# Power.net
KiCad netlist of a schematic drawn in Altium Designer
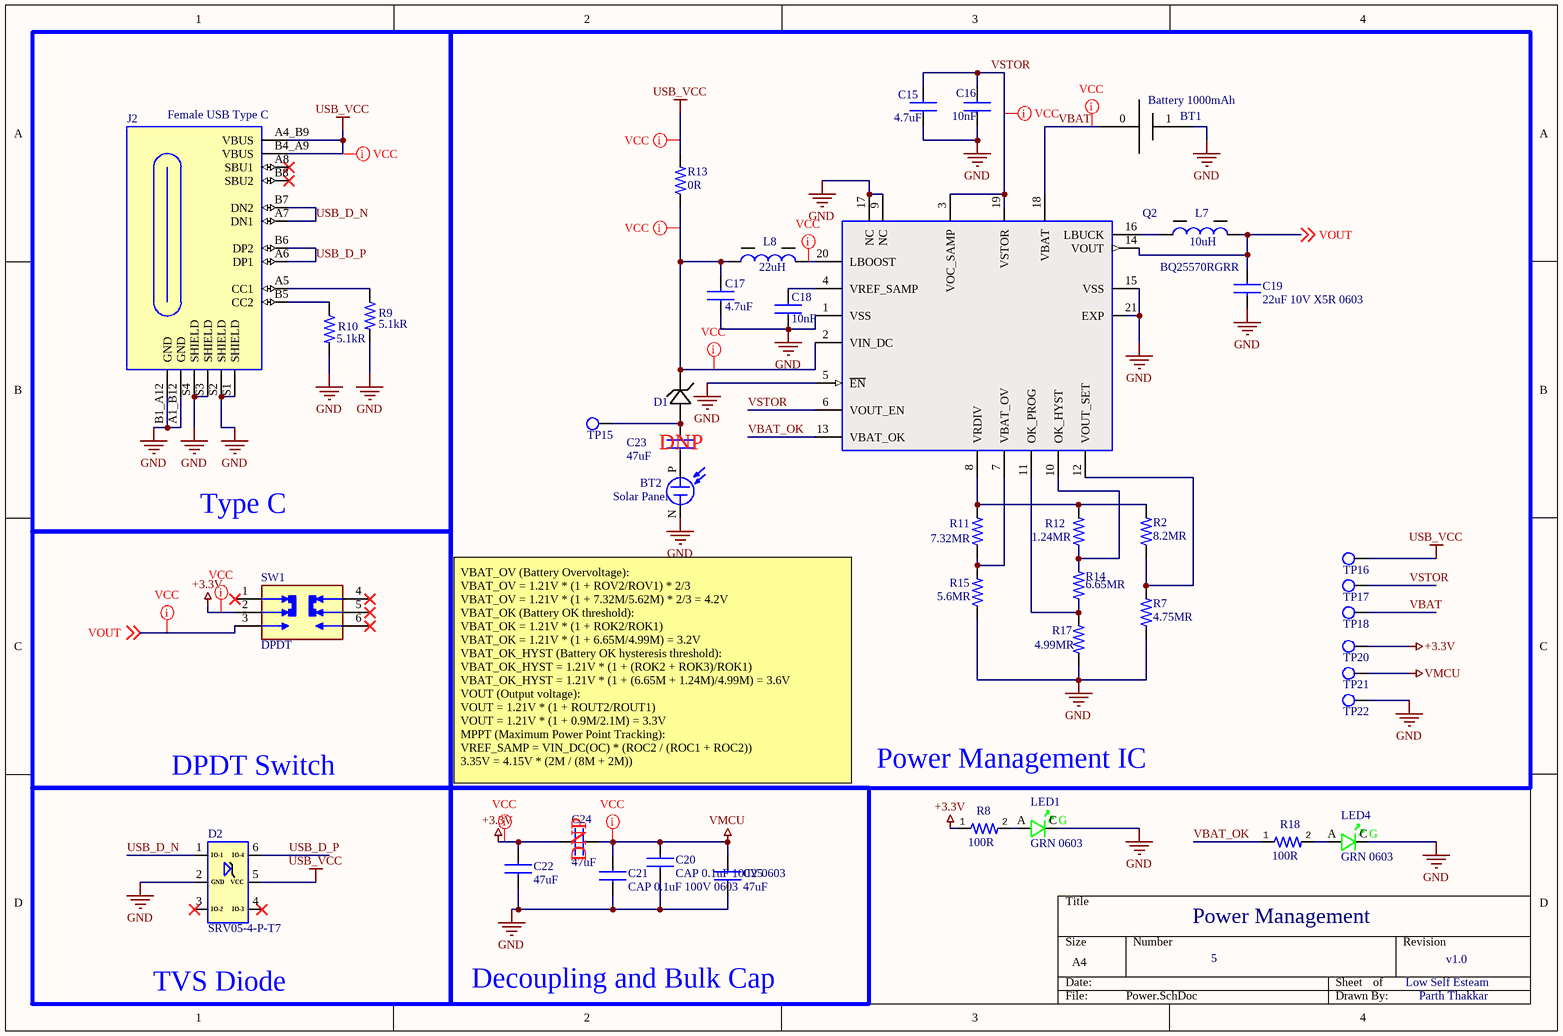
[diagram p0: Power.SchDoc]

(export (version "E")
  (design (tool "Eeschema 10.0.6"))
  (components
    (comp (ref "BT1")
      (value "Battery 1000mAh")
      (footprint "Battery")
      (description "Batt Lith-ion 3.7V 1.05AH 404852")
      (fields
        (field (name "MANUFACTURER") "GlobTek")
        (field (name "MANUFACTURER PART NUMBER") "BL1200P4054481S1PCAC")
      )
      (libsource (lib "Keyboard_parts") (part "Battery 1000mAh"))
    )
    (comp (ref "BT2")
      (value "Solar Panel")
      (footprint "Solar panel")
      (description "Monocryst Solar Cell 184MW 4.15V")
      (fields (field (name "MANUFACTURER") "ANYSOLAR") (field (name "MANUFACTURER PART NUMBER") "SM141K06L"))
      (libsource (lib "Keyboard_parts") (part "Solar Panel"))
    )
    (comp (ref "C15")
      (value "4.7uF")
      (footprint "Capacitor 0603")
      (fields
        (field (name "MANUFACTURER") "Murata")
        (field (name "MANUFACTURER PART NUMBER") "GRT188R61E475KE13D")
        (field (name "Comment") "CAP 4.7uF 25V 0603")
      )
      (libsource (lib "Keyboard_parts") (part "CAP 4.7uF 25V 0603"))
    )
    (comp (ref "C16")
      (value "10nF")
      (footprint "Capacitor 0603")
      (fields
        (field (name "MANUFACTURER") "Murata")
        (field (name "MANUFACTURER PART NUMBER") "GCM188R72A103KA37D")
        (field (name "Comment") "CAP 10nF 100V 0603")
      )
      (libsource (lib "Keyboard_parts") (part "CAP 10nF 100V 0603"))
    )
    (comp (ref "C17")
      (value "4.7uF")
      (footprint "Capacitor 0603")
      (fields
        (field (name "MANUFACTURER") "Murata")
        (field (name "MANUFACTURER PART NUMBER") "GRT188R61E475KE13D")
        (field (name "Comment") "CAP 4.7uF 25V 0603")
      )
      (libsource (lib "Keyboard_parts") (part "CAP 4.7uF 25V 0603"))
    )
    (comp (ref "C18")
      (value "10nF")
      (footprint "Capacitor 0603")
      (fields
        (field (name "MANUFACTURER") "Murata")
        (field (name "MANUFACTURER PART NUMBER") "GCM188R72A103KA37D")
        (field (name "Comment") "CAP 10nF 100V 0603")
      )
      (libsource (lib "Keyboard_parts") (part "CAP 10nF 100V 0603"))
    )
    (comp (ref "C19")
      (value "22uF 10V X5R 0603")
      (footprint "Capacitor 0603")
      (fields
        (field (name "MANUFACTURER") "Murata")
        (field (name "MANUFACTURER PART NUMBER") "GRM188R61A226ME15D")
        (field (name "TOLERANCE") "20 %")
      )
      (libsource (lib "Keyboard_parts") (part "CAP 22uF 6.3V 0603"))
    )
    (comp (ref "C20")
      (value "CAP 0.1uF 100V 0603")
      (footprint "Capacitor 0603")
      (fields
        (field (name "MANUFACTURER") "Murata")
        (field (name "MANUFACTURER PART NUMBER") "GCM188R72A103KA37D")
      )
      (libsource (lib "Keyboard_parts") (part "CAP 0.1uF 100V 0603"))
    )
    (comp (ref "C21")
      (value "CAP 0.1uF 100V 0603")
      (footprint "Capacitor 0603")
      (fields
        (field (name "MANUFACTURER") "Murata")
        (field (name "MANUFACTURER PART NUMBER") "GCM188R72A103KA37D")
      )
      (libsource (lib "Keyboard_parts") (part "CAP 0.1uF 100V 0603"))
    )
    (comp (ref "C22")
      (value "47uF")
      (footprint "Capacitor 0805")
      (description "Multilayer Ceramic Capacitors MLCC - SMD/SMT 0805 47uF 10volts *Derate Voltage/Temp")
      (fields
        (field (name "MANUFACTURER") "Murata")
        (field (name "MANUFACTURER PART NUMBER") "GRM21BR61A476ME15K")
      )
      (libsource (lib "Keyboard_parts") (part "CAP 47uF 10V 0805"))
    )
    (comp (ref "C23")
      (value "47uF")
      (footprint "CAPACITOR 0805")
      (description "Multilayer Ceramic Capacitors MLCC - SMD/SMT 0805 47uF 10volts *Derate Voltage/Temp")
      (fields
        (field (name "MANUFACTURER") "Murata")
        (field (name "MANUFACTURER PART NUMBER") "GRM21BR61A476ME15K")
      )
      (libsource (lib "InsaneIntegratedLib") (part "CAP 47uF 10V 0805"))
    )
    (comp (ref "C24")
      (value "47uF")
      (footprint "CAPACITOR 0805")
      (description "Multilayer Ceramic Capacitors MLCC - SMD/SMT 0805 47uF 10volts *Derate Voltage/Temp")
      (fields
        (field (name "MANUFACTURER") "Murata")
        (field (name "MANUFACTURER PART NUMBER") "GRM21BR61A476ME15K")
      )
      (libsource (lib "InsaneIntegratedLib") (part "CAP 47uF 10V 0805"))
    )
    (comp (ref "C25")
      (value "47uF")
      (footprint "Capacitor 0805")
      (description "Multilayer Ceramic Capacitors MLCC - SMD/SMT 0805 47uF 10volts *Derate Voltage/Temp")
      (fields
        (field (name "MANUFACTURER") "Murata")
        (field (name "MANUFACTURER PART NUMBER") "GRM21BR61A476ME15K")
      )
      (libsource (lib "Keyboard_parts") (part "CAP 47uF 10V 0805"))
    )
    (comp (ref "D1")
      (value "Diode Schottky")
      (footprint "Diode Schottky")
      (description "Rectifier Diode, Schottky, 1 Phase, 1 Element, 1A, 15V V(RRM), Silicon, DO-214BA")
      (fields
        (field (name "MANUFACTURER") "Microchip")
        (field (name "MANUFACTURER PART NUMBER") "LSM115JE3/TR13")
      )
      (libsource (lib "InsaneIntegratedLib") (part "Diode Schottky"))
    )
    (comp (ref "D2")
      (value "SRV05-4-P-T7")
      (footprint "TVS")
      (description "Trans Voltage Suppressor Diode, 300W, 5V V(RWM), Unidirectional, 1 Element, Silicon")
      (fields (field (name "LCSC PART#") "C85364") (field (name "MANUFACTURER") "Semtech"))
      (libsource (lib "Keyboard_parts") (part "D_TVS_Diode"))
    )
    (comp (ref "J2")
      (value "Female USB Type C")
      (footprint "Type C")
      (fields (field (name "MANUFACTURER PART NUMBER") "USB4125-GF-A_REVA2"))
      (libsource (lib "Keyboard_parts") (part "USB-C Power Connector"))
    )
    (comp (ref "L7")
      (value "IND 10uH 1111")
      (footprint "IND 10uH (1x3.2)")
      (description "General Purpose Inductor, 10uH, 30%, 1 Element, Ferrite-Core, SMD, 1111")
      (fields
        (field (name "MANUFACTURER") "Wurth Electronics")
        (field (name "MANUFACTURER PART NUMBER") "744029100")
        (field (name "INDUCTANCE-NOM (L)") "10uH")
      )
      (libsource (lib "Keyboard_parts") (part "IND 10uH 1111"))
    )
    (comp (ref "L8")
      (value "IND 22uH 1515")
      (footprint "IND 22uH (1.6x4.3)")
      (description "General Purpose Inductor, 22uH, 30%, 1 Element, Ferrite-Core, SMD, 1515")
      (fields
        (field (name "MANUFACTURER") "Wurth Electronics")
        (field (name "MANUFACTURER PART NUMBER") "744031220")
        (field (name "INDUCTANCE-NOM (L)") "22uH")
      )
      (libsource (lib "Keyboard_parts") (part "IND 22uH 1515"))
    )
    (comp (ref "LED1")
      (value "GRN 0603")
      (footprint "LED 0603")
      (description "LED, 0603, GREEN, 430MCD, 520NM")
      (fields
        (field (name "MANUFACTURER") "Wurth Electronics")
        (field (name "MANUFACTURER PART NUMBER") "150060GS75000")
      )
      (libsource (lib "InsaneIntegratedLib") (part "LED Green 0603"))
    )
    (comp (ref "LED4")
      (value "GRN 0603")
      (footprint "LED 0603")
      (description "LED, 0603, GREEN, 430MCD, 520NM")
      (fields
        (field (name "MANUFACTURER") "Wurth Electronics")
        (field (name "MANUFACTURER PART NUMBER") "150060GS75000")
      )
      (libsource (lib "InsaneIntegratedLib") (part "LED Green 0603"))
    )
    (comp (ref "Q2")
      (value "BQ25570RGRR")
      (footprint "BQ25570RGRR")
      (description "Power Supply Support Circuit, Adjustable, 1 Channel, PQCC20")
      (fields (field (name "MANUFACTURER") "Texas Instruments"))
      (libsource (lib "Keyboard_parts") (part "BQ25570RGRR"))
    )
    (comp (ref "R2")
      (value "8.2MR")
      (footprint "Resistor 0603")
      (fields
        (field (name "MANUFACTURER") "Yageo")
        (field (name "MANUFACTURER PART NUMBER") "RC0603JR-078M2L")
        (field (name "TOLERANCE") "5%")
      )
      (libsource (lib "InsaneIntegratedLib") (part "RES 8.2M 0603"))
    )
    (comp (ref "R7")
      (value "4.75MR")
      (footprint "Resistor 0603")
      (fields
        (field (name "MANUFACTURER") "Yageo")
        (field (name "MANUFACTURER PART NUMBER") "RC0603FR-074M75L")
        (field (name "TOLERANCE") "1%")
      )
      (libsource (lib "InsaneIntegratedLib") (part "RES 4.75M 0603"))
    )
    (comp (ref "R8")
      (value "100R")
      (footprint "Resistor 0603")
      (fields
        (field (name "MANUFACTURER") "Yageo")
        (field (name "MANUFACTURER PART NUMBER") "RC0603FR-07100RL")
        (field (name "TOLERANCE") "1%")
      )
      (libsource (lib "InsaneIntegratedLib") (part "RES 100R 0603"))
    )
    (comp (ref "R9")
      (value "5.1kR")
      (footprint "Resistor 0603")
      (fields
        (field (name "MANUFACTURER") "Yageo")
        (field (name "MANUFACTURER PART NUMBER") "RC0603FR-075K1L")
        (field (name "TOLERANCE") "1%")
      )
      (libsource (lib "Keyboard_parts") (part "RES 5.1K 0603"))
    )
    (comp (ref "R10")
      (value "5.1kR")
      (footprint "Resistor 0603")
      (fields
        (field (name "MANUFACTURER") "Yageo")
        (field (name "MANUFACTURER PART NUMBER") "RC0603FR-075K1L")
        (field (name "TOLERANCE") "1%")
      )
      (libsource (lib "Keyboard_parts") (part "RES 5.1K 0603"))
    )
    (comp (ref "R11")
      (value "7.32MR")
      (footprint "Resistor 0603")
      (fields
        (field (name "MANUFACTURER") "Yageo")
        (field (name "MANUFACTURER PART NUMBER") "RC0402FR-077M32L")
        (field (name "TOLERANCE") "1%")
      )
      (libsource (lib "Keyboard_parts") (part "RES 7.32M 0603"))
    )
    (comp (ref "R12")
      (value "1.24MR")
      (footprint "Resistor 0603")
      (fields
        (field (name "MANUFACTURER") "Yageo")
        (field (name "MANUFACTURER PART NUMBER") "RC0603FR-071M24L")
        (field (name "TOLERANCE") "1%")
      )
      (libsource (lib "Keyboard_parts") (part "RES 1.24M 0603"))
    )
    (comp (ref "R13")
      (value "0R")
      (footprint "Resistor 0402")
      (description "Metal Glaze/thick Film, 0.0625W, 0ohm, Surface Mount, 0402")
      (fields
        (field (name "MANUFACTURER") "Yageo")
        (field (name "MANUFACTURER PART NUMBER") "RC0402JR-070RL")
      )
      (libsource (lib "Keyboard_parts") (part "RES 0R 0402"))
    )
    (comp (ref "R14")
      (value "6.65MR")
      (footprint "Resistor 0603")
      (fields
        (field (name "MANUFACTURER") "Vishay")
        (field (name "MANUFACTURER PART NUMBER") "CRCW06036M65FKEA")
        (field (name "TOLERANCE") "1%")
      )
      (libsource (lib "Keyboard_parts") (part "RES 6.65M 0603"))
    )
    (comp (ref "R15")
      (value "5.6MR")
      (footprint "Resistor 0603")
      (fields
        (field (name "MANUFACTURER") "Yageo")
        (field (name "MANUFACTURER PART NUMBER") "RC0603JR-075M6L")
        (field (name "TOLERANCE") "5%")
      )
      (libsource (lib "Keyboard_parts") (part "RES 5.62M 0603"))
    )
    (comp (ref "R17")
      (value "4.99MR")
      (footprint "Resistor 0603")
      (fields
        (field (name "MANUFACTURER") "Yageo")
        (field (name "MANUFACTURER PART NUMBER") "RC0603FR-074M99L")
        (field (name "TOLERANCE") "1%")
      )
      (libsource (lib "Keyboard_parts") (part "RES 4.99M 0603"))
    )
    (comp (ref "R18")
      (value "100R")
      (footprint "Resistor 0603")
      (fields
        (field (name "MANUFACTURER") "Yageo")
        (field (name "MANUFACTURER PART NUMBER") "RC0603FR-07100RL")
        (field (name "TOLERANCE") "1%")
      )
      (libsource (lib "InsaneIntegratedLib") (part "RES 100R 0603"))
    )
    (comp (ref "SW1")
      (value "DPDT")
      (footprint "DPDT")
      (description "Slide Switch, DPDT, Latched, Solder Terminal, Through Hole-right Angle")
      (fields (field (name "MANUFACTURER") "E-Switch") (field (name "MANUFACTURER PART NUMBER") "EG2208"))
      (libsource (lib "Keyboard_parts") (part "DPDT"))
    )
    (comp (ref "TP15")
      (value "Test Point")
      (footprint "Test point")
      (description "Test points")
      (libsource (lib "Keyboard_parts") (part "Test Point"))
    )
    (comp (ref "TP16")
      (value "Test point")
      (footprint "Test Point")
      (libsource (lib "Keyboard_parts") (part "Test point"))
    )
    (comp (ref "TP17")
      (value "Test point")
      (footprint "Test Point")
      (libsource (lib "Keyboard_parts") (part "Test point"))
    )
    (comp (ref "TP18")
      (value "Test point")
      (footprint "Test Point")
      (libsource (lib "Keyboard_parts") (part "Test point"))
    )
    (comp (ref "TP20")
      (value "Test point")
      (footprint "Test Point")
      (libsource (lib "Keyboard_parts") (part "Test point"))
    )
    (comp (ref "TP21")
      (value "Test point")
      (footprint "Test Point")
      (libsource (lib "Keyboard_parts") (part "Test point"))
    )
    (comp (ref "TP22")
      (value "Test point")
      (footprint "Test Point")
      (libsource (lib "Keyboard_parts") (part "Test point"))
    )
  )
  (nets
    (net (code "1") (name "+3.3V") (class "Default")
      (node (ref "C22") (pin "1") (pinfunction "1_1") (pintype "passive"))
      (node (ref "C24") (pin "1") (pinfunction "1_1") (pintype "passive"))
      (node (ref "R8") (pin "1") (pinfunction "1_1") (pintype "passive"))
      (node (ref "SW1") (pin "2") (pinfunction "2_2") (pintype "passive"))
      (node (ref "TP20") (pin "1") (pinfunction "1_1") (pintype "passive"))
    )
    (net (code "2") (name "/USB_D_N") (class "Default")
      (node (ref "D2") (pin "1") (pinfunction "IO-1_1") (pintype "passive"))
      (node (ref "J2") (pin "A7") (pinfunction "DN1_A7") (pintype "bidirectional"))
      (node (ref "J2") (pin "B7") (pinfunction "DN2_B7") (pintype "bidirectional"))
    )
    (net (code "3") (name "/USB_D_P") (class "Default")
      (node (ref "D2") (pin "6") (pinfunction "IO-4_6") (pintype "passive"))
      (node (ref "J2") (pin "A6") (pinfunction "DP1_A6") (pintype "bidirectional"))
      (node (ref "J2") (pin "B6") (pinfunction "DP2_B6") (pintype "bidirectional"))
    )
    (net (code "4") (name "/VBAT") (class "Default")
      (node (ref "BT1") (pin "0") (pinfunction "VCC_0") (pintype "passive"))
      (node (ref "Q2") (pin "18") (pinfunction "VBAT_18") (pintype "power_in"))
      (node (ref "TP18") (pin "1") (pinfunction "1_1") (pintype "passive"))
    )
    (net (code "5") (name "/VBAT_OK") (class "Default")
      (node (ref "Q2") (pin "13") (pinfunction "VBAT_OK_13") (pintype "passive"))
      (node (ref "R18") (pin "1") (pinfunction "1_1") (pintype "passive"))
    )
    (net (code "6") (name "/VSTOR") (class "Default")
      (node (ref "C15") (pin "1") (pinfunction "1_1") (pintype "passive"))
      (node (ref "C16") (pin "1") (pinfunction "1_1") (pintype "passive"))
      (node (ref "Q2") (pin "19") (pinfunction "VSTOR_19") (pintype "passive"))
      (node (ref "Q2") (pin "3") (pinfunction "VOC_SAMP_3") (pintype "passive"))
      (node (ref "Q2") (pin "6") (pinfunction "VOUT_EN_6") (pintype "passive"))
      (node (ref "TP17") (pin "1") (pinfunction "1_1") (pintype "passive"))
    )
    (net (code "7") (name "GND") (class "Default")
      (node (ref "BT1") (pin "1") (pinfunction "GND_1") (pintype "passive"))
      (node (ref "BT2") (pin "N") (pinfunction "N_N") (pintype "passive"))
      (node (ref "C15") (pin "2") (pinfunction "2_2") (pintype "passive"))
      (node (ref "C16") (pin "2") (pinfunction "2_2") (pintype "passive"))
      (node (ref "C17") (pin "2") (pinfunction "2_2") (pintype "passive"))
      (node (ref "C18") (pin "1") (pinfunction "1_1") (pintype "passive"))
      (node (ref "C19") (pin "2") (pinfunction "2_2") (pintype "passive"))
      (node (ref "C20") (pin "2") (pinfunction "2_2") (pintype "passive"))
      (node (ref "C21") (pin "2") (pinfunction "2_2") (pintype "passive"))
      (node (ref "C22") (pin "2") (pinfunction "2_2") (pintype "passive"))
      (node (ref "C25") (pin "2") (pinfunction "2_2") (pintype "passive"))
      (node (ref "D2") (pin "2") (pinfunction "GND_2") (pintype "passive"))
      (node (ref "J2") (pin "A1_B12") (pinfunction "GND_A1_B12") (pintype "power_in"))
      (node (ref "J2") (pin "B1_A12") (pinfunction "GND_B1_A12") (pintype "power_in"))
      (node (ref "J2") (pin "S1") (pinfunction "SHIELD_S1") (pintype "passive"))
      (node (ref "J2") (pin "S2") (pinfunction "SHIELD_S2") (pintype "passive"))
      (node (ref "J2") (pin "S3") (pinfunction "SHIELD_S3") (pintype "passive"))
      (node (ref "J2") (pin "S4") (pinfunction "SHIELD_S4") (pintype "passive"))
      (node (ref "LED1") (pin "C") (pinfunction "C_C") (pintype "passive"))
      (node (ref "LED4") (pin "C") (pinfunction "C_C") (pintype "passive"))
      (node (ref "Q2") (pin "1") (pinfunction "VSS_1") (pintype "passive"))
      (node (ref "Q2") (pin "15") (pinfunction "VSS_15") (pintype "passive"))
      (node (ref "Q2") (pin "17") (pinfunction "NC_17") (pintype "passive"))
      (node (ref "Q2") (pin "21") (pinfunction "EXP_21") (pintype "passive"))
      (node (ref "Q2") (pin "5") (pinfunction "~{EN}_5") (pintype "input"))
      (node (ref "Q2") (pin "9") (pinfunction "NC_9") (pintype "passive"))
      (node (ref "R10") (pin "2") (pinfunction "2_2") (pintype "passive"))
      (node (ref "R15") (pin "1") (pinfunction "1_1") (pintype "passive"))
      (node (ref "R17") (pin "1") (pinfunction "1_1") (pintype "passive"))
      (node (ref "R7") (pin "1") (pinfunction "1_1") (pintype "passive"))
      (node (ref "R9") (pin "2") (pinfunction "2_2") (pintype "passive"))
      (node (ref "TP22") (pin "1") (pinfunction "1_1") (pintype "passive"))
    )
    (net (code "8") (name "Net-(BT2-PadP)") (class "Default")
      (node (ref "BT2") (pin "P") (pinfunction "P_P") (pintype "passive"))
      (node (ref "C23") (pin "2") (pinfunction "2_2") (pintype "passive"))
    )
    (net (code "9") (name "Net-(C23-Pad1)") (class "Default")
      (node (ref "C23") (pin "1") (pinfunction "1_1") (pintype "passive"))
      (node (ref "D1") (pin "2") (pinfunction "2_2") (pintype "passive"))
      (node (ref "TP15") (pin "1") (pinfunction "1_1") (pintype "passive"))
    )
    (net (code "10") (name "Net-(J2-CC1)") (class "Default")
      (node (ref "J2") (pin "A5") (pinfunction "CC1_A5") (pintype "bidirectional"))
      (node (ref "R9") (pin "1") (pinfunction "1_1") (pintype "passive"))
    )
    (net (code "11") (name "Net-(J2-CC2)") (class "Default")
      (node (ref "J2") (pin "B5") (pinfunction "CC2_B5") (pintype "bidirectional"))
      (node (ref "R10") (pin "1") (pinfunction "1_1") (pintype "passive"))
    )
    (net (code "12") (name "Net-(LED1-PadA)") (class "Default")
      (node (ref "LED1") (pin "A") (pinfunction "A_A") (pintype "passive"))
      (node (ref "R8") (pin "2") (pinfunction "2_2") (pintype "passive"))
    )
    (net (code "13") (name "Net-(LED4-PadA)") (class "Default")
      (node (ref "LED4") (pin "A") (pinfunction "A_A") (pintype "passive"))
      (node (ref "R18") (pin "2") (pinfunction "2_2") (pintype "passive"))
    )
    (net (code "14") (name "Net-(Q2-LBOOST)") (class "Default")
      (node (ref "L8") (pin "2") (pinfunction "2_2") (pintype "passive"))
      (node (ref "Q2") (pin "20") (pinfunction "LBOOST_20") (pintype "power_in"))
    )
    (net (code "15") (name "Net-(Q2-LBUCK)") (class "Default")
      (node (ref "L7") (pin "1") (pinfunction "1_1") (pintype "passive"))
      (node (ref "Q2") (pin "16") (pinfunction "LBUCK_16") (pintype "power_in"))
    )
    (net (code "16") (name "Net-(Q2-OK_HYST)") (class "Default")
      (node (ref "Q2") (pin "10") (pinfunction "OK_HYST_10") (pintype "power_in"))
      (node (ref "R12") (pin "1") (pinfunction "1_1") (pintype "passive"))
      (node (ref "R14") (pin "2") (pinfunction "2_2") (pintype "passive"))
    )
    (net (code "17") (name "Net-(Q2-OK_PROG)") (class "Default")
      (node (ref "Q2") (pin "11") (pinfunction "OK_PROG_11") (pintype "power_in"))
      (node (ref "R14") (pin "1") (pinfunction "1_1") (pintype "passive"))
      (node (ref "R17") (pin "2") (pinfunction "2_2") (pintype "passive"))
    )
    (net (code "18") (name "Net-(Q2-VBAT_OV)") (class "Default")
      (node (ref "Q2") (pin "7") (pinfunction "VBAT_OV_7") (pintype "passive"))
      (node (ref "R11") (pin "1") (pinfunction "1_1") (pintype "passive"))
      (node (ref "R15") (pin "2") (pinfunction "2_2") (pintype "passive"))
    )
    (net (code "19") (name "Net-(Q2-VIN_DC)") (class "Default")
      (node (ref "C17") (pin "1") (pinfunction "1_1") (pintype "passive"))
      (node (ref "D1") (pin "1") (pinfunction "1_1") (pintype "passive"))
      (node (ref "L8") (pin "1") (pinfunction "1_1") (pintype "passive"))
      (node (ref "Q2") (pin "2") (pinfunction "VIN_DC_2") (pintype "passive"))
      (node (ref "R13") (pin "1") (pinfunction "1_1") (pintype "passive"))
    )
    (net (code "20") (name "Net-(Q2-VOUT_SET)") (class "Default")
      (node (ref "Q2") (pin "12") (pinfunction "VOUT_SET_12") (pintype "passive"))
      (node (ref "R2") (pin "1") (pinfunction "1_1") (pintype "passive"))
      (node (ref "R7") (pin "2") (pinfunction "2_2") (pintype "passive"))
    )
    (net (code "21") (name "Net-(Q2-VRDIV)") (class "Default")
      (node (ref "Q2") (pin "8") (pinfunction "VRDIV_8") (pintype "passive"))
      (node (ref "R11") (pin "2") (pinfunction "2_2") (pintype "passive"))
      (node (ref "R12") (pin "2") (pinfunction "2_2") (pintype "passive"))
      (node (ref "R2") (pin "2") (pinfunction "2_2") (pintype "passive"))
    )
    (net (code "22") (name "Net-(Q2-VREF_SAMP)") (class "Default")
      (node (ref "C18") (pin "2") (pinfunction "2_2") (pintype "passive"))
      (node (ref "Q2") (pin "4") (pinfunction "VREF_SAMP_4") (pintype "passive"))
    )
    (net (code "23") (name "USB_VCC") (class "Default")
      (node (ref "D2") (pin "5") (pinfunction "VCC_5") (pintype "passive"))
      (node (ref "J2") (pin "A4_B9") (pinfunction "VBUS_A4_B9") (pintype "power_in"))
      (node (ref "J2") (pin "B4_A9") (pinfunction "VBUS_B4_A9") (pintype "power_in"))
      (node (ref "R13") (pin "2") (pinfunction "2_2") (pintype "passive"))
      (node (ref "TP16") (pin "1") (pinfunction "1_1") (pintype "passive"))
    )
    (net (code "24") (name "VMCU") (class "Default")
      (node (ref "C20") (pin "1") (pinfunction "1_1") (pintype "passive"))
      (node (ref "C21") (pin "1") (pinfunction "1_1") (pintype "passive"))
      (node (ref "C24") (pin "2") (pinfunction "2_2") (pintype "passive"))
      (node (ref "C25") (pin "1") (pinfunction "1_1") (pintype "passive"))
      (node (ref "TP21") (pin "1") (pinfunction "1_1") (pintype "passive"))
    )
    (net (code "25") (name "VOUT") (class "Default")
      (node (ref "C19") (pin "1") (pinfunction "1_1") (pintype "passive"))
      (node (ref "L7") (pin "2") (pinfunction "2_2") (pintype "passive"))
      (node (ref "Q2") (pin "14") (pinfunction "VOUT_14") (pintype "output"))
      (node (ref "SW1") (pin "3") (pinfunction "3_3") (pintype "passive"))
    )
    (net (code "26") (name "unconnected-(D2-IO-2-Pad3)") (class "Default")
      (node (ref "D2") (pin "3") (pinfunction "IO-2_3") (pintype "passive+no_connect"))
    )
    (net (code "27") (name "unconnected-(D2-IO-3-Pad4)") (class "Default")
      (node (ref "D2") (pin "4") (pinfunction "IO-3_4") (pintype "passive+no_connect"))
    )
    (net (code "28") (name "unconnected-(J2-SBU1-PadA8)") (class "Default")
      (node (ref "J2") (pin "A8") (pinfunction "SBU1_A8") (pintype "bidirectional+no_connect"))
    )
    (net (code "29") (name "unconnected-(J2-SBU2-PadB8)") (class "Default")
      (node (ref "J2") (pin "B8") (pinfunction "SBU2_B8") (pintype "bidirectional+no_connect"))
    )
    (net (code "30") (name "unconnected-(SW1-Pad1)") (class "Default")
      (node (ref "SW1") (pin "1") (pinfunction "1_1") (pintype "passive+no_connect"))
    )
    (net (code "31") (name "unconnected-(SW1-Pad4)") (class "Default")
      (node (ref "SW1") (pin "4") (pinfunction "4_4") (pintype "passive+no_connect"))
    )
    (net (code "32") (name "unconnected-(SW1-Pad5)") (class "Default")
      (node (ref "SW1") (pin "5") (pinfunction "5_5") (pintype "passive+no_connect"))
    )
    (net (code "33") (name "unconnected-(SW1-Pad6)") (class "Default")
      (node (ref "SW1") (pin "6") (pinfunction "6_6") (pintype "passive+no_connect"))
    )
  )
)
